# node-v2.net
KiCad netlist of a schematic drawn in EAGLE
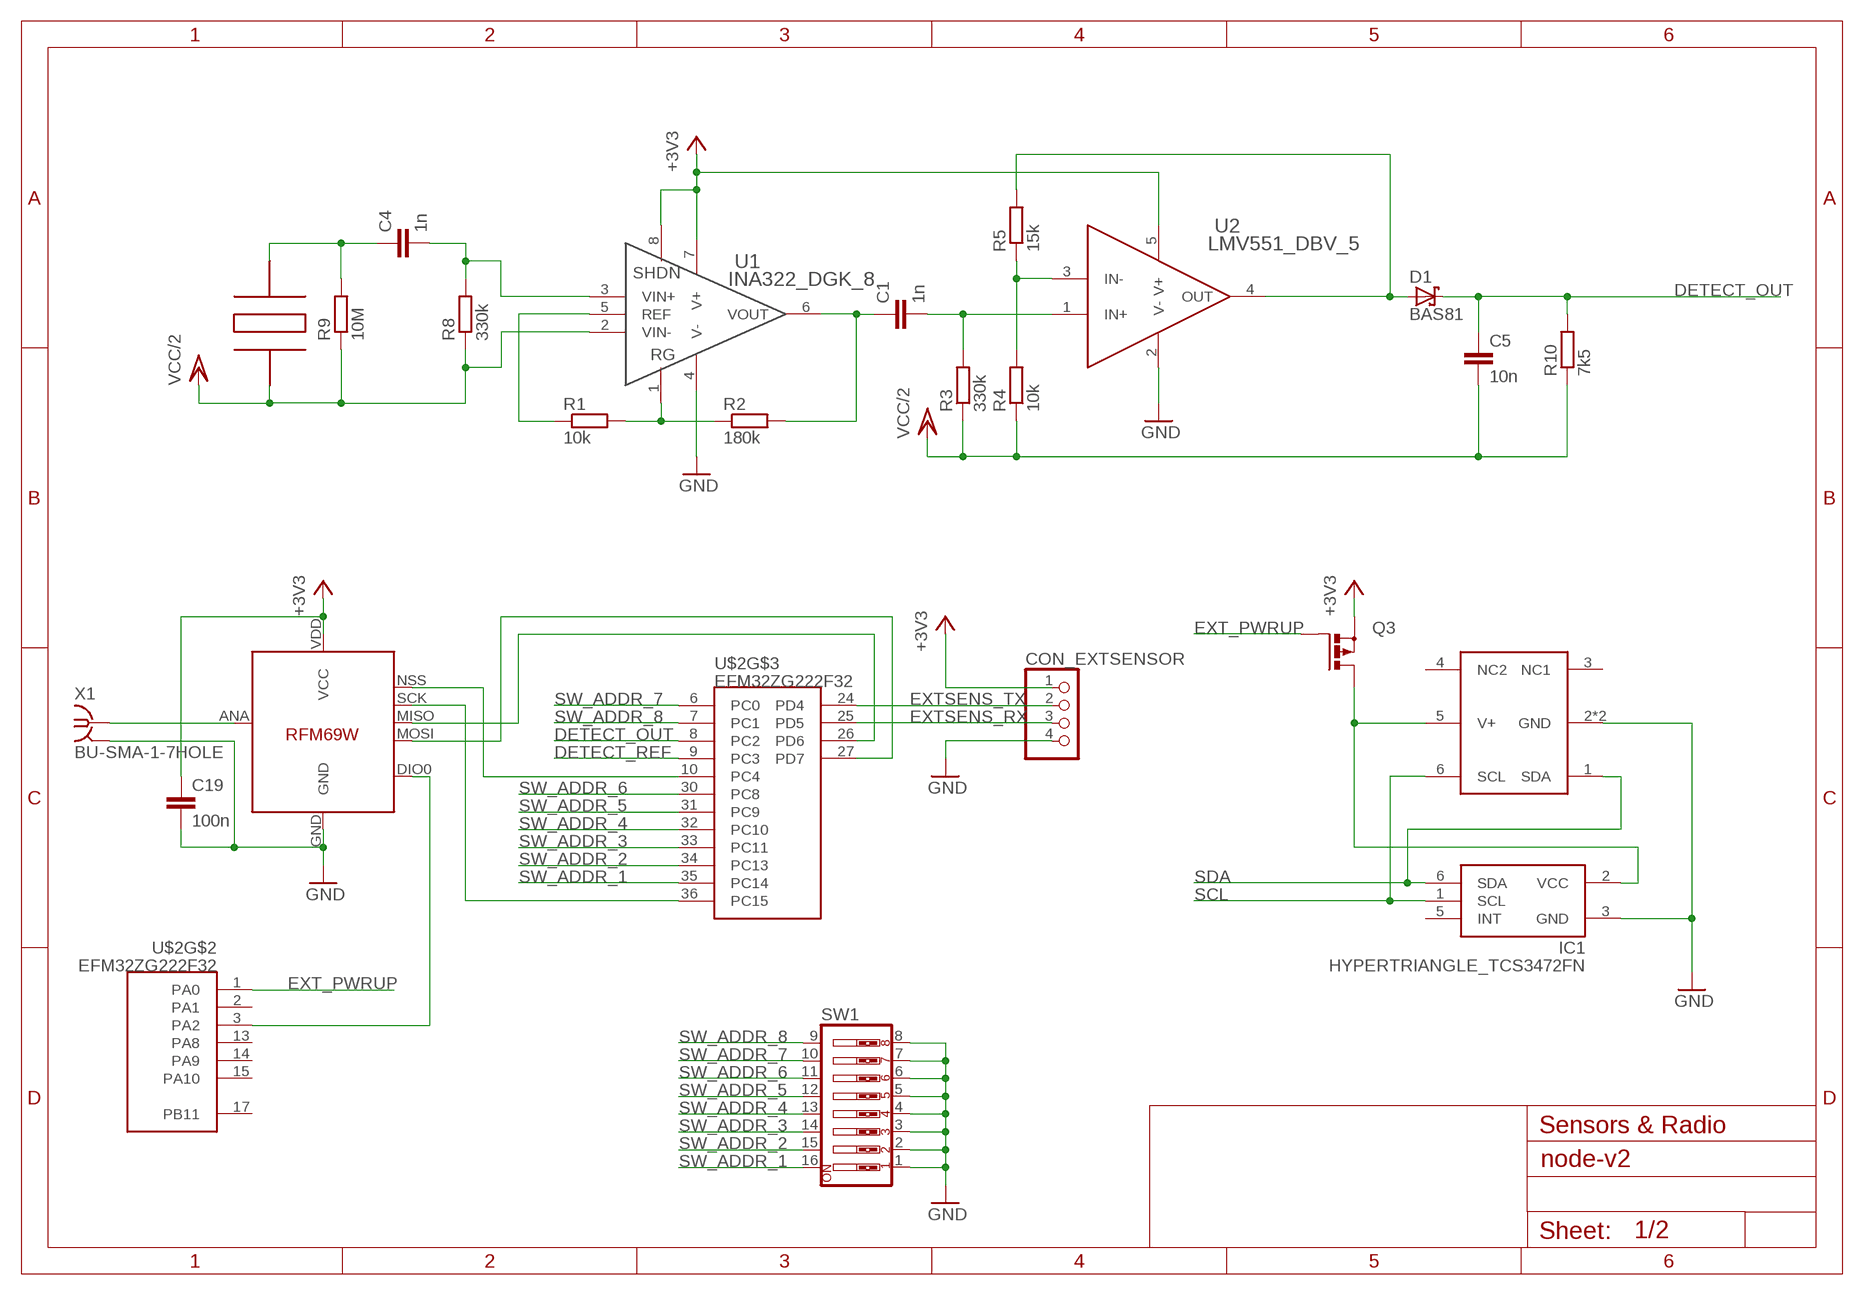
[diagram p0: schematic, sheet 1]
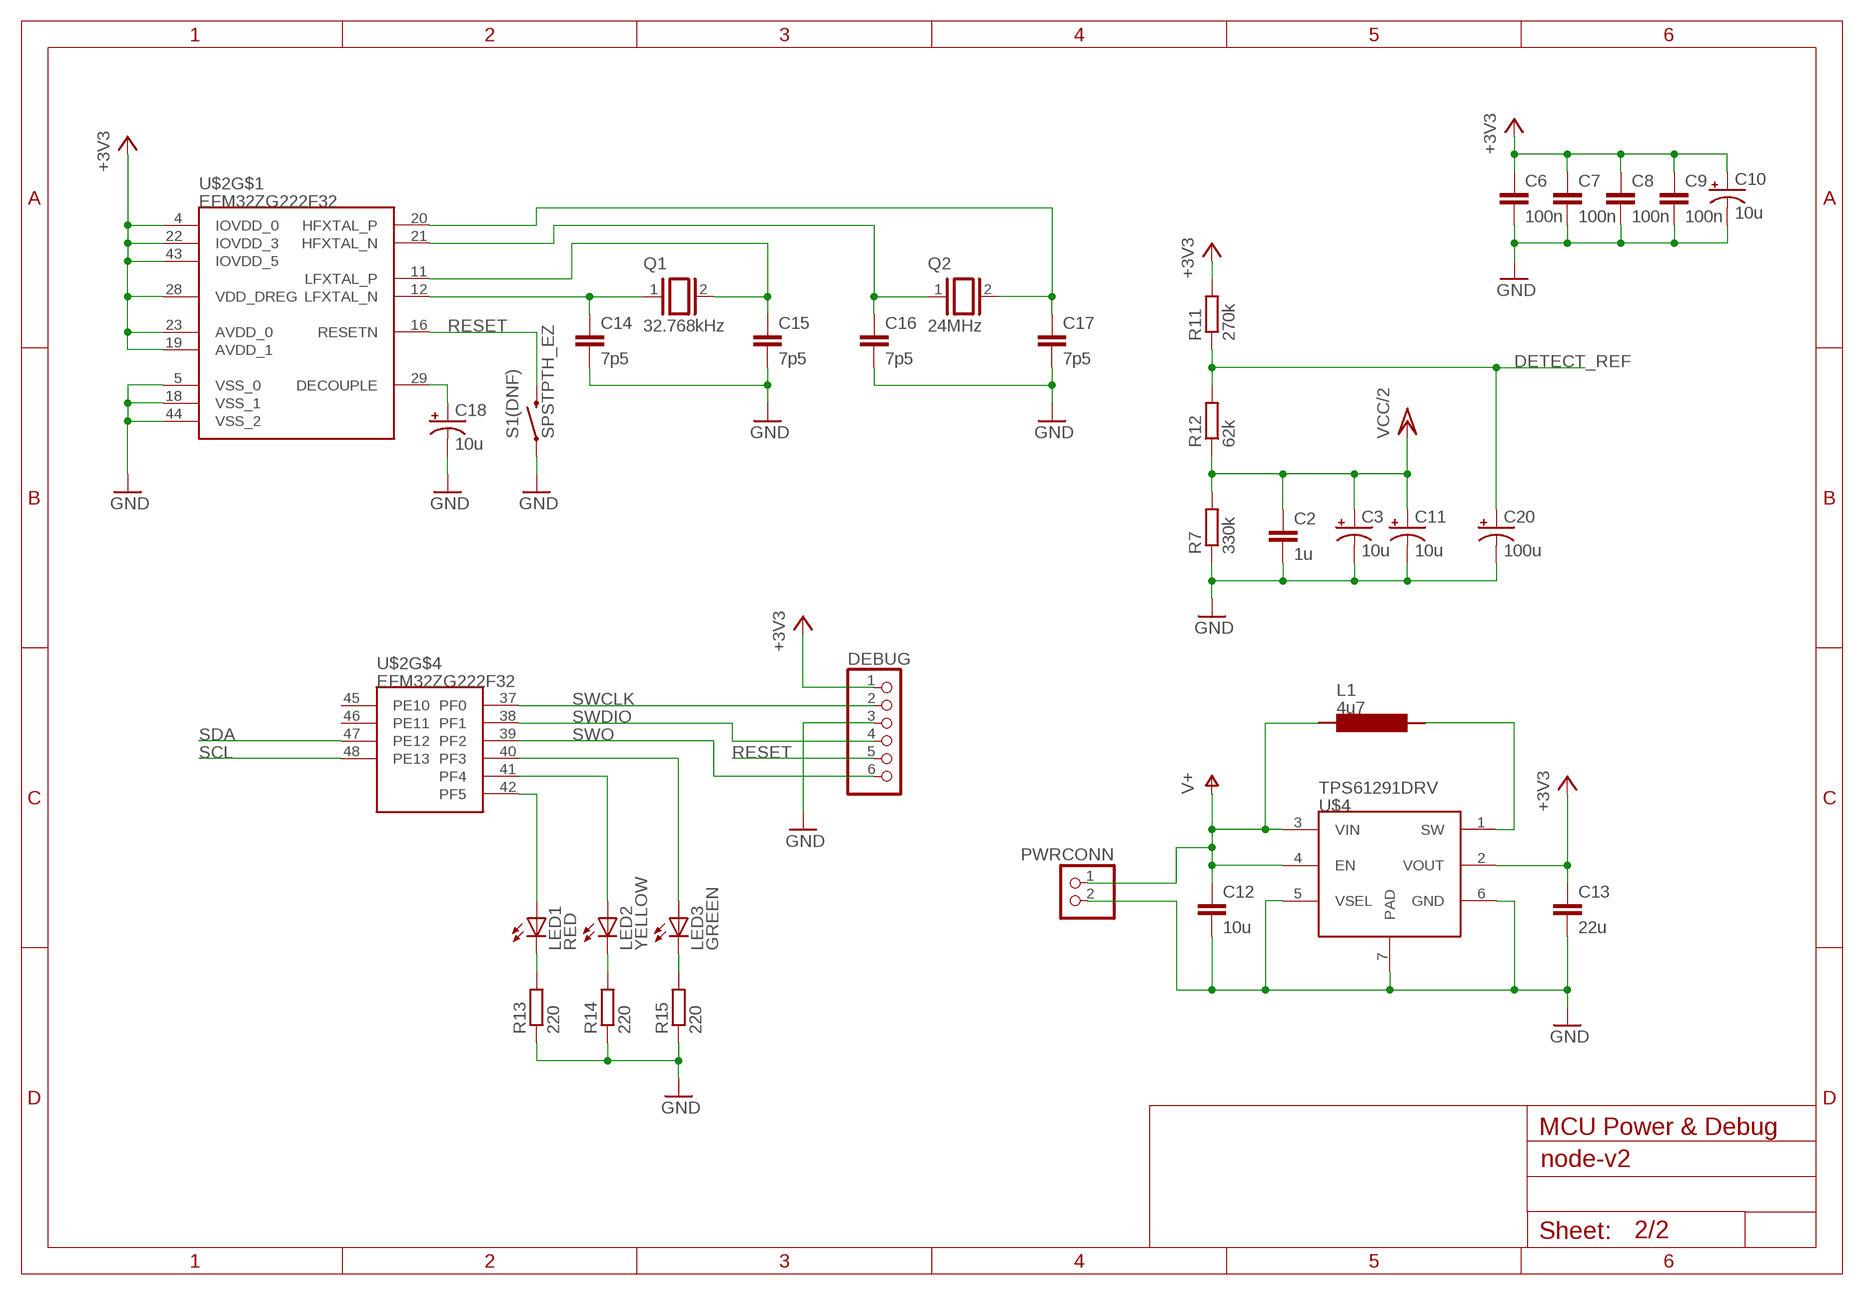
[diagram p1: schematic, sheet 2]

(export (version "E")
  (design (tool "Eeschema 10.0.6"))
  (components
    (comp (ref "C2")
      (value "1u")
      (footprint "eagle-import:CAP-PTH-SMALL")
      (libsource (lib "eagle-import") (part "CAPPTH"))
    )
    (comp (ref "C3")
      (value "10u")
      (footprint "eagle-import:CPOL-RADIAL-10UF-25V")
      (libsource (lib "eagle-import") (part "CAP_POLPTH2"))
    )
    (comp (ref "C6")
      (value "100n")
      (footprint "eagle-import:CAP-PTH-SMALL")
      (libsource (lib "eagle-import") (part "CAPPTH"))
    )
    (comp (ref "C7")
      (value "100n")
      (footprint "eagle-import:CAP-PTH-5MM")
      (libsource (lib "eagle-import") (part "CAPPTH1"))
    )
    (comp (ref "C8")
      (value "100n")
      (footprint "eagle-import:CAP-PTH-SMALL")
      (libsource (lib "eagle-import") (part "CAPPTH"))
    )
    (comp (ref "C9")
      (value "100n")
      (footprint "eagle-import:CAP-PTH-SMALL")
      (libsource (lib "eagle-import") (part "CAPPTH"))
    )
    (comp (ref "C10")
      (value "10u")
      (footprint "eagle-import:CPOL-RADIAL-10UF-25V")
      (libsource (lib "eagle-import") (part "CAP_POLPTH2"))
    )
    (comp (ref "C11")
      (value "10u")
      (footprint "eagle-import:CPOL-RADIAL-10UF-25V")
      (libsource (lib "eagle-import") (part "CAP_POLPTH2"))
    )
    (comp (ref "C12")
      (value "10u")
      (footprint "eagle-import:1206")
      (libsource (lib "eagle-import") (part "CAP1206"))
    )
    (comp (ref "C13")
      (value "22u")
      (footprint "eagle-import:1206")
      (libsource (lib "eagle-import") (part "CAP1206"))
    )
    (comp (ref "C14")
      (value "7p5")
      (footprint "eagle-import:CAP-PTH-SMALL")
      (libsource (lib "eagle-import") (part "CAPPTH"))
    )
    (comp (ref "C15")
      (value "7p5")
      (footprint "eagle-import:CAP-PTH-SMALL")
      (libsource (lib "eagle-import") (part "CAPPTH"))
    )
    (comp (ref "C16")
      (value "7p5")
      (footprint "eagle-import:CAP-PTH-SMALL")
      (libsource (lib "eagle-import") (part "CAPPTH"))
    )
    (comp (ref "C17")
      (value "7p5")
      (footprint "eagle-import:CAP-PTH-SMALL")
      (libsource (lib "eagle-import") (part "CAPPTH"))
    )
    (comp (ref "C18")
      (value "10u")
      (footprint "eagle-import:CPOL-RADIAL-10UF-25V")
      (libsource (lib "eagle-import") (part "CAP_POLPTH2"))
    )
    (comp (ref "C20")
      (value "100u")
      (footprint "eagle-import:CPOL-RADIAL-10UF-25V")
      (libsource (lib "eagle-import") (part "CAP_POLPTH2"))
    )
    (comp (ref "DEBUG")
      (value "PINHD-1X6")
      (footprint "eagle-import:1X06")
      (libsource (lib "eagle-import") (part "PINHD-1X6"))
    )
    (comp (ref "L1")
      (value "4u7")
      (footprint "eagle-import:LTF5022")
      (libsource (lib "eagle-import") (part "LTF5022"))
    )
    (comp (ref "LED1")
      (value "RED")
      (footprint "eagle-import:LED3MM")
      (libsource (lib "eagle-import") (part "LED3MM"))
    )
    (comp (ref "LED2")
      (value "YELLOW")
      (footprint "eagle-import:LED3MM")
      (libsource (lib "eagle-import") (part "LED3MM"))
    )
    (comp (ref "LED3")
      (value "GREEN")
      (footprint "eagle-import:LED3MM")
      (libsource (lib "eagle-import") (part "LED3MM"))
    )
    (comp (ref "PWRCONN")
      (value "PINHD-1X2")
      (footprint "eagle-import:1X02")
      (libsource (lib "eagle-import") (part "PINHD-1X2"))
    )
    (comp (ref "Q1")
      (value "32.768kHz")
      (footprint "eagle-import:QS")
      (libsource (lib "eagle-import") (part "XTAL/S"))
    )
    (comp (ref "Q2")
      (value "24MHz")
      (footprint "eagle-import:QS")
      (libsource (lib "eagle-import") (part "XTAL/S"))
    )
    (comp (ref "R7")
      (value "330k")
      (footprint "eagle-import:0204_7")
      (libsource (lib "eagle-import") (part "R-EU_0204/7"))
    )
    (comp (ref "R11")
      (value "270k")
      (footprint "eagle-import:0204_7")
      (libsource (lib "eagle-import") (part "R-EU_0204/7"))
    )
    (comp (ref "R12")
      (value "62k")
      (footprint "eagle-import:0204_7")
      (libsource (lib "eagle-import") (part "R-EU_0204/7"))
    )
    (comp (ref "R13")
      (value "220")
      (footprint "eagle-import:0204_7")
      (libsource (lib "eagle-import") (part "R-EU_0204/7"))
    )
    (comp (ref "R14")
      (value "220")
      (footprint "eagle-import:0204_7")
      (libsource (lib "eagle-import") (part "R-EU_0204/7"))
    )
    (comp (ref "R15")
      (value "220")
      (footprint "eagle-import:0204_7")
      (libsource (lib "eagle-import") (part "R-EU_0204/7"))
    )
    (comp (ref "S1(DNF)")
      (value "SPSTPTH_EZ")
      (footprint "eagle-import:TACTILE-PTH-EZ")
      (libsource (lib "eagle-import") (part "SPSTPTH_EZ"))
    )
    (comp (ref "U$2")
      (value "EFM32ZG222F32")
      (footprint "eagle-import:QFP48")
      (libsource (lib "eagle-import") (part "EFM32ZG222F32"))
    )
    (comp (ref "U$4")
      (value "TPS61291DRV")
      (footprint "eagle-import:DRV0006A")
      (libsource (lib "eagle-import") (part "TPS61291DRV"))
    )
    (comp (ref "C1")
      (value "1n")
      (footprint "eagle-import:CAP-PTH-SMALL")
      (libsource (lib "eagle-import") (part "CAPPTH"))
    )
    (comp (ref "C4")
      (value "1n")
      (footprint "eagle-import:CAP-PTH-SMALL")
      (libsource (lib "eagle-import") (part "CAPPTH"))
    )
    (comp (ref "C5")
      (value "10n")
      (footprint "eagle-import:CAP-PTH-SMALL")
      (libsource (lib "eagle-import") (part "CAPPTH"))
    )
    (comp (ref "C19")
      (value "100n")
      (footprint "eagle-import:CAP-PTH-SMALL")
      (libsource (lib "eagle-import") (part "CAPPTH"))
    )
    (comp (ref "CON_EXTSENSOR")
      (value "PINHD-1X4")
      (footprint "eagle-import:1X04")
      (libsource (lib "eagle-import") (part "PINHD-1X4"))
    )
    (comp (ref "D1")
      (value "BAS81")
      (footprint "eagle-import:DO35-7")
      (libsource (lib "eagle-import") (part "SCHOTTKY-DIODEDO35-7"))
    )
    (comp (ref "IC1")
      (value "HYPERTRIANGLE_TCS3472FN")
      (footprint "eagle-import:HYPERTRIANGLE_DFN-6")
      (libsource (lib "eagle-import") (part "HYPERTRIANGLE_TCS3472FN"))
    )
    (comp (ref "Q3")
      (value "PMOSFET_PTO220BH")
      (footprint "eagle-import:TO220BH")
      (libsource (lib "eagle-import") (part "PMOSFET_PTO220BH"))
    )
    (comp (ref "R1")
      (value "10k")
      (footprint "eagle-import:0204_7")
      (libsource (lib "eagle-import") (part "R-EU_0204/7"))
    )
    (comp (ref "R2")
      (value "180k")
      (footprint "eagle-import:0204_7")
      (libsource (lib "eagle-import") (part "R-EU_0204/7"))
    )
    (comp (ref "R3")
      (value "330k")
      (footprint "eagle-import:0204_7")
      (libsource (lib "eagle-import") (part "R-EU_0204/7"))
    )
    (comp (ref "R4")
      (value "10k")
      (footprint "eagle-import:0204_7")
      (libsource (lib "eagle-import") (part "R-EU_0204/7"))
    )
    (comp (ref "R5")
      (value "15k")
      (footprint "eagle-import:0204_7")
      (libsource (lib "eagle-import") (part "R-EU_0204/7"))
    )
    (comp (ref "R8")
      (value "330k")
      (footprint "eagle-import:0204_7")
      (libsource (lib "eagle-import") (part "R-EU_0204/7"))
    )
    (comp (ref "R9")
      (value "10M")
      (footprint "eagle-import:0204_7")
      (libsource (lib "eagle-import") (part "R-EU_0204/7"))
    )
    (comp (ref "R10")
      (value "7k5")
      (footprint "eagle-import:0204_7")
      (libsource (lib "eagle-import") (part "R-EU_0204/7"))
    )
    (comp (ref "RADIO")
      (value "RFM69")
      (footprint "eagle-import:RFM69W-MINPADS")
      (libsource (lib "eagle-import") (part "RFM69"))
    )
    (comp (ref "SW1")
      (value "SW_DIP-8")
      (footprint "eagle-import:DIPSWITCH-08")
      (libsource (lib "eagle-import") (part "SW_DIP-8"))
    )
    (comp (ref "U$1")
      (value "PIEZOWIREHEADER")
      (footprint "eagle-import:1X02")
      (libsource (lib "eagle-import") (part "PIEZOWIREHEADER"))
    )
    (comp (ref "U$3")
      (value "SHT21")
      (footprint "eagle-import:SHT21")
      (libsource (lib "eagle-import") (part "SHT21"))
    )
    (comp (ref "U1")
      (value "INA322_DGK_8")
      (footprint "eagle-import:DGK8")
      (fields
        (field (name "GENERIC_PART_NUMBER") "INA322")
        (field (name "MANUFACTURER") "Texas Instruments")
        (field (name "MANUFACTURER_PART_NUMBER") "ina322_dgk_8")
      )
      (libsource (lib "eagle-import") (part "INA322_DGK_8"))
    )
    (comp (ref "U2")
      (value "LMV551_DBV_5")
      (footprint "eagle-import:MF05A")
      (libsource (lib "eagle-import") (part "LMV551_DBV_5"))
    )
    (comp (ref "X1")
      (value "BU-SMA-1-7HOLE")
      (footprint "eagle-import:SMA_1-7HOLES")
      (libsource (lib "eagle-import") (part "BU-SMA-1-7HOLE"))
    )
  )
  (nets
    (net (code "1") (name "+3V3") (class "Default")
      (node (ref "C10") (pin "1") (pinfunction "+_1") (pintype "passive"))
      (node (ref "C13") (pin "1") (pinfunction "1_1") (pintype "passive"))
      (node (ref "C19") (pin "1") (pinfunction "1_1") (pintype "passive"))
      (node (ref "C6") (pin "1") (pinfunction "1_1") (pintype "passive"))
      (node (ref "C7") (pin "1") (pinfunction "1_1") (pintype "passive"))
      (node (ref "C8") (pin "1") (pinfunction "1_1") (pintype "passive"))
      (node (ref "C9") (pin "1") (pinfunction "1_1") (pintype "passive"))
      (node (ref "CON_EXTSENSOR") (pin "1") (pinfunction "1_1") (pintype "passive"))
      (node (ref "DEBUG") (pin "1") (pinfunction "1_1") (pintype "passive"))
      (node (ref "Q3") (pin "S") (pinfunction "S_S") (pintype "passive"))
      (node (ref "R11") (pin "2") (pinfunction "2_2") (pintype "passive"))
      (node (ref "RADIO") (pin "VDD") (pinfunction "VCC_VDD") (pintype "power_in"))
      (node (ref "U$2") (pin "19") (pinfunction "AVDD_1_19") (pintype "power_in"))
      (node (ref "U$2") (pin "22") (pinfunction "IOVDD_3_22") (pintype "power_in"))
      (node (ref "U$2") (pin "23") (pinfunction "AVDD_0_23") (pintype "power_in"))
      (node (ref "U$2") (pin "28") (pinfunction "VDD_DREG_28") (pintype "power_in"))
      (node (ref "U$2") (pin "4") (pinfunction "IOVDD_0_4") (pintype "power_in"))
      (node (ref "U$2") (pin "43") (pinfunction "IOVDD_5_43") (pintype "power_in"))
      (node (ref "U$4") (pin "2") (pinfunction "VOUT_2") (pintype "bidirectional"))
      (node (ref "U1") (pin "7") (pinfunction "V+_7") (pintype "power_in"))
      (node (ref "U1") (pin "8") (pinfunction "SHDN_8") (pintype "passive"))
      (node (ref "U2") (pin "5") (pinfunction "V+_5") (pintype "power_in"))
    )
    (net (code "2") (name "DETECT_OUT") (class "Default")
      (node (ref "C5") (pin "1") (pinfunction "1_1") (pintype "passive"))
      (node (ref "D1") (pin "C") (pinfunction "C_C") (pintype "passive"))
      (node (ref "R10") (pin "2") (pinfunction "2_2") (pintype "passive"))
      (node (ref "U$2") (pin "8") (pinfunction "PC2_8") (pintype "bidirectional"))
    )
    (net (code "3") (name "DETECT_REF") (class "Default")
      (node (ref "C20") (pin "1") (pinfunction "+_1") (pintype "passive"))
      (node (ref "R11") (pin "1") (pinfunction "1_1") (pintype "passive"))
      (node (ref "R12") (pin "2") (pinfunction "2_2") (pintype "passive"))
      (node (ref "U$2") (pin "9") (pinfunction "PC3_9") (pintype "bidirectional"))
    )
    (net (code "4") (name "EXTSENS_RX") (class "Default")
      (node (ref "CON_EXTSENSOR") (pin "3") (pinfunction "3_3") (pintype "passive"))
      (node (ref "U$2") (pin "25") (pinfunction "PD5_25") (pintype "bidirectional"))
    )
    (net (code "5") (name "EXTSENS_TX") (class "Default")
      (node (ref "CON_EXTSENSOR") (pin "2") (pinfunction "2_2") (pintype "passive"))
      (node (ref "U$2") (pin "24") (pinfunction "PD4_24") (pintype "bidirectional"))
    )
    (net (code "6") (name "EXT_PWRUP") (class "Default")
      (node (ref "Q3") (pin "G") (pinfunction "G_G") (pintype "passive"))
      (node (ref "U$2") (pin "1") (pinfunction "PA0_1") (pintype "bidirectional"))
    )
    (net (code "7") (name "GND") (class "Default")
      (node (ref "C10") (pin "2") (pinfunction "-_2") (pintype "passive"))
      (node (ref "C11") (pin "2") (pinfunction "-_2") (pintype "passive"))
      (node (ref "C12") (pin "2") (pinfunction "2_2") (pintype "passive"))
      (node (ref "C13") (pin "2") (pinfunction "2_2") (pintype "passive"))
      (node (ref "C14") (pin "2") (pinfunction "2_2") (pintype "passive"))
      (node (ref "C15") (pin "2") (pinfunction "2_2") (pintype "passive"))
      (node (ref "C16") (pin "2") (pinfunction "2_2") (pintype "passive"))
      (node (ref "C17") (pin "2") (pinfunction "2_2") (pintype "passive"))
      (node (ref "C18") (pin "2") (pinfunction "-_2") (pintype "passive"))
      (node (ref "C19") (pin "2") (pinfunction "2_2") (pintype "passive"))
      (node (ref "C2") (pin "2") (pinfunction "2_2") (pintype "passive"))
      (node (ref "C20") (pin "2") (pinfunction "-_2") (pintype "passive"))
      (node (ref "C3") (pin "2") (pinfunction "-_2") (pintype "passive"))
      (node (ref "C6") (pin "2") (pinfunction "2_2") (pintype "passive"))
      (node (ref "C7") (pin "2") (pinfunction "2_2") (pintype "passive"))
      (node (ref "C8") (pin "2") (pinfunction "2_2") (pintype "passive"))
      (node (ref "C9") (pin "2") (pinfunction "2_2") (pintype "passive"))
      (node (ref "CON_EXTSENSOR") (pin "4") (pinfunction "4_4") (pintype "passive"))
      (node (ref "DEBUG") (pin "3") (pinfunction "3_3") (pintype "passive"))
      (node (ref "IC1") (pin "3") (pinfunction "GND_3") (pintype "power_in"))
      (node (ref "PWRCONN") (pin "2") (pinfunction "2_2") (pintype "passive"))
      (node (ref "R13") (pin "1") (pinfunction "1_1") (pintype "passive"))
      (node (ref "R14") (pin "1") (pinfunction "1_1") (pintype "passive"))
      (node (ref "R15") (pin "1") (pinfunction "1_1") (pintype "passive"))
      (node (ref "R7") (pin "1") (pinfunction "1_1") (pintype "passive"))
      (node (ref "RADIO") (pin "GND") (pinfunction "GND_GND") (pintype "power_in"))
      (node (ref "S1(DNF)") (pin "1") (pinfunction "1_1") (pintype "passive"))
      (node (ref "SW1") (pin "1") (pinfunction "1_1") (pintype "passive"))
      (node (ref "SW1") (pin "2") (pinfunction "2_2") (pintype "passive"))
      (node (ref "SW1") (pin "3") (pinfunction "3_3") (pintype "passive"))
      (node (ref "SW1") (pin "4") (pinfunction "4_4") (pintype "passive"))
      (node (ref "SW1") (pin "5") (pinfunction "5_5") (pintype "passive"))
      (node (ref "SW1") (pin "6") (pinfunction "6_6") (pintype "passive"))
      (node (ref "SW1") (pin "7") (pinfunction "7_7") (pintype "passive"))
      (node (ref "SW1") (pin "8") (pinfunction "8_8") (pintype "passive"))
      (node (ref "U$2") (pin "18") (pinfunction "VSS_1_18") (pintype "bidirectional"))
      (node (ref "U$2") (pin "44") (pinfunction "VSS_2_44") (pintype "bidirectional"))
      (node (ref "U$2") (pin "5") (pinfunction "VSS_0_5") (pintype "bidirectional"))
      (node (ref "U$3") (pin "2") (pinfunction "GND_2") (pintype "bidirectional"))
      (node (ref "U$3") (pin "P$1") (pinfunction "GND_P$1") (pintype "bidirectional"))
      (node (ref "U$4") (pin "5") (pinfunction "VSEL_5") (pintype "bidirectional"))
      (node (ref "U$4") (pin "6") (pinfunction "GND_6") (pintype "bidirectional"))
      (node (ref "U$4") (pin "7") (pinfunction "PAD_7") (pintype "bidirectional"))
      (node (ref "U1") (pin "4") (pinfunction "V-_4") (pintype "power_in"))
      (node (ref "U2") (pin "2") (pinfunction "V-_2") (pintype "power_in"))
      (node (ref "X1") (pin "2") (pinfunction "2_2") (pintype "passive"))
      (node (ref "X1") (pin "3") (pinfunction "2_3") (pintype "passive"))
      (node (ref "X1") (pin "4") (pinfunction "2_4") (pintype "passive"))
      (node (ref "X1") (pin "5") (pinfunction "2_5") (pintype "passive"))
    )
    (net (code "8") (name "Net-(C18-+)") (class "Default")
      (node (ref "C18") (pin "1") (pinfunction "+_1") (pintype "passive"))
      (node (ref "U$2") (pin "29") (pinfunction "DECOUPLE_29") (pintype "power_in"))
    )
    (net (code "9") (name "Net-(IC1-VCC)") (class "Default")
      (node (ref "IC1") (pin "2") (pinfunction "VCC_2") (pintype "power_in"))
      (node (ref "Q3") (pin "D") (pinfunction "D_D") (pintype "passive"))
      (node (ref "U$3") (pin "5") (pinfunction "V+_5") (pintype "bidirectional"))
    )
    (net (code "10") (name "Net-(LED1-C)") (class "Default")
      (node (ref "LED1") (pin "K") (pinfunction "C_K") (pintype "passive"))
      (node (ref "R13") (pin "2") (pinfunction "2_2") (pintype "passive"))
    )
    (net (code "11") (name "Net-(LED2-C)") (class "Default")
      (node (ref "LED2") (pin "K") (pinfunction "C_K") (pintype "passive"))
      (node (ref "R14") (pin "2") (pinfunction "2_2") (pintype "passive"))
    )
    (net (code "12") (name "Net-(LED3-C)") (class "Default")
      (node (ref "LED3") (pin "K") (pinfunction "C_K") (pintype "passive"))
      (node (ref "R15") (pin "2") (pinfunction "2_2") (pintype "passive"))
    )
    (net (code "13") (name "Net-(RADIO-ANT)") (class "Default")
      (node (ref "RADIO") (pin "ANA") (pinfunction "ANT_ANA") (pintype "passive"))
      (node (ref "X1") (pin "1") (pinfunction "1_1") (pintype "passive"))
    )
    (net (code "14") (name "Net-(RADIO-SEL)") (class "Default")
      (node (ref "RADIO") (pin "NSS") (pinfunction "SEL_NSS") (pintype "input"))
      (node (ref "U$2") (pin "10") (pinfunction "PC4_10") (pintype "bidirectional"))
    )
    (net (code "15") (name "Net-(U$1-S+)") (class "Default")
      (node (ref "C4") (pin "1") (pinfunction "1_1") (pintype "passive"))
      (node (ref "R9") (pin "2") (pinfunction "2_2") (pintype "passive"))
      (node (ref "U$1") (pin "1") (pinfunction "S+_1") (pintype "passive"))
    )
    (net (code "16") (name "Net-(U$2A-HFXTAL_N)") (class "Default")
      (node (ref "C16") (pin "1") (pinfunction "1_1") (pintype "passive"))
      (node (ref "Q2") (pin "1") (pinfunction "1_1") (pintype "passive"))
      (node (ref "U$2") (pin "21") (pinfunction "HFXTAL_N_21") (pintype "bidirectional"))
    )
    (net (code "17") (name "Net-(U$2A-HFXTAL_P)") (class "Default")
      (node (ref "C17") (pin "1") (pinfunction "1_1") (pintype "passive"))
      (node (ref "Q2") (pin "2") (pinfunction "2_2") (pintype "passive"))
      (node (ref "U$2") (pin "20") (pinfunction "HFXTAL_P_20") (pintype "bidirectional"))
    )
    (net (code "18") (name "Net-(U$2A-LFXTAL_N)") (class "Default")
      (node (ref "C14") (pin "1") (pinfunction "1_1") (pintype "passive"))
      (node (ref "Q1") (pin "1") (pinfunction "1_1") (pintype "passive"))
      (node (ref "U$2") (pin "12") (pinfunction "LFXTAL_N_12") (pintype "bidirectional"))
    )
    (net (code "19") (name "Net-(U$2A-LFXTAL_P)") (class "Default")
      (node (ref "C15") (pin "1") (pinfunction "1_1") (pintype "passive"))
      (node (ref "Q1") (pin "2") (pinfunction "2_2") (pintype "passive"))
      (node (ref "U$2") (pin "11") (pinfunction "LFXTAL_P_11") (pintype "bidirectional"))
    )
    (net (code "20") (name "Net-(U$2B-PA2)") (class "Default")
      (node (ref "RADIO") (pin "DIO0") (pinfunction "DIO0_DIO0") (pintype "open_collector"))
      (node (ref "U$2") (pin "3") (pinfunction "PA2_3") (pintype "bidirectional"))
    )
    (net (code "21") (name "Net-(U$2C-PC15)") (class "Default")
      (node (ref "RADIO") (pin "SCK") (pinfunction "SCK_SCK") (pintype "input"))
      (node (ref "U$2") (pin "36") (pinfunction "PC15_36") (pintype "bidirectional"))
    )
    (net (code "22") (name "Net-(U$2C-PD6)") (class "Default")
      (node (ref "RADIO") (pin "MISO") (pinfunction "MISO_MISO") (pintype "input"))
      (node (ref "U$2") (pin "26") (pinfunction "PD6_26") (pintype "bidirectional"))
    )
    (net (code "23") (name "Net-(U$2C-PD7)") (class "Default")
      (node (ref "RADIO") (pin "MOSI") (pinfunction "MOSI_MOSI") (pintype "output"))
      (node (ref "U$2") (pin "27") (pinfunction "PD7_27") (pintype "bidirectional"))
    )
    (net (code "24") (name "Net-(U$2D-PF3)") (class "Default")
      (node (ref "LED3") (pin "A") (pinfunction "A_A") (pintype "passive"))
      (node (ref "U$2") (pin "40") (pinfunction "PF3_40") (pintype "bidirectional"))
    )
    (net (code "25") (name "Net-(U$2D-PF4)") (class "Default")
      (node (ref "LED2") (pin "A") (pinfunction "A_A") (pintype "passive"))
      (node (ref "U$2") (pin "41") (pinfunction "PF4_41") (pintype "bidirectional"))
    )
    (net (code "26") (name "Net-(U$2D-PF5)") (class "Default")
      (node (ref "LED1") (pin "A") (pinfunction "A_A") (pintype "passive"))
      (node (ref "U$2") (pin "42") (pinfunction "PF5_42") (pintype "bidirectional"))
    )
    (net (code "27") (name "Net-(U$4-SW)") (class "Default")
      (node (ref "L1") (pin "2") (pinfunction "2_2") (pintype "passive"))
      (node (ref "U$4") (pin "1") (pinfunction "SW_1") (pintype "bidirectional"))
    )
    (net (code "28") (name "Net-(U1-REF)") (class "Default")
      (node (ref "R1") (pin "1") (pinfunction "1_1") (pintype "passive"))
      (node (ref "U1") (pin "5") (pinfunction "REF_5") (pintype "passive"))
    )
    (net (code "29") (name "Net-(U1-RG)") (class "Default")
      (node (ref "R1") (pin "2") (pinfunction "2_2") (pintype "passive"))
      (node (ref "R2") (pin "1") (pinfunction "1_1") (pintype "passive"))
      (node (ref "U1") (pin "1") (pinfunction "RG_1") (pintype "passive"))
    )
    (net (code "30") (name "Net-(U1-VIN+)") (class "Default")
      (node (ref "C4") (pin "2") (pinfunction "2_2") (pintype "passive"))
      (node (ref "R8") (pin "2") (pinfunction "2_2") (pintype "passive"))
      (node (ref "U1") (pin "3") (pinfunction "VIN+_3") (pintype "input"))
    )
    (net (code "31") (name "Net-(U1-VOUT)") (class "Default")
      (node (ref "C1") (pin "1") (pinfunction "1_1") (pintype "passive"))
      (node (ref "R2") (pin "2") (pinfunction "2_2") (pintype "passive"))
      (node (ref "U1") (pin "6") (pinfunction "VOUT_6") (pintype "output"))
    )
    (net (code "32") (name "Net-(U2-IN+)") (class "Default")
      (node (ref "C1") (pin "2") (pinfunction "2_2") (pintype "passive"))
      (node (ref "R3") (pin "2") (pinfunction "2_2") (pintype "passive"))
      (node (ref "U2") (pin "1") (pinfunction "IN+_1") (pintype "input"))
    )
    (net (code "33") (name "Net-(U2-IN-)") (class "Default")
      (node (ref "R4") (pin "2") (pinfunction "2_2") (pintype "passive"))
      (node (ref "R5") (pin "1") (pinfunction "1_1") (pintype "passive"))
      (node (ref "U2") (pin "3") (pinfunction "IN-_3") (pintype "input"))
    )
    (net (code "34") (name "Net-(U2-OUT)") (class "Default")
      (node (ref "D1") (pin "A") (pinfunction "A_A") (pintype "passive"))
      (node (ref "R5") (pin "2") (pinfunction "2_2") (pintype "passive"))
      (node (ref "U2") (pin "4") (pinfunction "OUT_4") (pintype "output"))
    )
    (net (code "35") (name "RESET") (class "Default")
      (node (ref "DEBUG") (pin "5") (pinfunction "5_5") (pintype "passive"))
      (node (ref "S1(DNF)") (pin "3") (pinfunction "2_3") (pintype "passive"))
      (node (ref "U$2") (pin "16") (pinfunction "RESETN_16") (pintype "power_in"))
    )
    (net (code "36") (name "SCL") (class "Default")
      (node (ref "IC1") (pin "1") (pinfunction "SCL_1") (pintype "bidirectional"))
      (node (ref "U$2") (pin "48") (pinfunction "PE13_48") (pintype "bidirectional"))
      (node (ref "U$3") (pin "6") (pinfunction "SCL_6") (pintype "bidirectional"))
    )
    (net (code "37") (name "SDA") (class "Default")
      (node (ref "IC1") (pin "6") (pinfunction "SDA_6") (pintype "bidirectional"))
      (node (ref "U$2") (pin "47") (pinfunction "PE12_47") (pintype "bidirectional"))
      (node (ref "U$3") (pin "1") (pinfunction "SDA_1") (pintype "bidirectional"))
    )
    (net (code "38") (name "SWCLK") (class "Default")
      (node (ref "DEBUG") (pin "2") (pinfunction "2_2") (pintype "passive"))
      (node (ref "U$2") (pin "37") (pinfunction "PF0_37") (pintype "bidirectional"))
    )
    (net (code "39") (name "SWDIO") (class "Default")
      (node (ref "DEBUG") (pin "4") (pinfunction "4_4") (pintype "passive"))
      (node (ref "U$2") (pin "38") (pinfunction "PF1_38") (pintype "bidirectional"))
    )
    (net (code "40") (name "SWO") (class "Default")
      (node (ref "DEBUG") (pin "6") (pinfunction "6_6") (pintype "passive"))
      (node (ref "U$2") (pin "39") (pinfunction "PF2_39") (pintype "bidirectional"))
    )
    (net (code "41") (name "SW_ADDR_1") (class "Default")
      (node (ref "SW1") (pin "16") (pinfunction "16_16") (pintype "passive"))
      (node (ref "U$2") (pin "35") (pinfunction "PC14_35") (pintype "bidirectional"))
    )
    (net (code "42") (name "SW_ADDR_2") (class "Default")
      (node (ref "SW1") (pin "15") (pinfunction "15_15") (pintype "passive"))
      (node (ref "U$2") (pin "34") (pinfunction "PC13_34") (pintype "bidirectional"))
    )
    (net (code "43") (name "SW_ADDR_3") (class "Default")
      (node (ref "SW1") (pin "14") (pinfunction "14_14") (pintype "passive"))
      (node (ref "U$2") (pin "33") (pinfunction "PC11_33") (pintype "bidirectional"))
    )
    (net (code "44") (name "SW_ADDR_4") (class "Default")
      (node (ref "SW1") (pin "13") (pinfunction "13_13") (pintype "passive"))
      (node (ref "U$2") (pin "32") (pinfunction "PC10_32") (pintype "bidirectional"))
    )
    (net (code "45") (name "SW_ADDR_5") (class "Default")
      (node (ref "SW1") (pin "12") (pinfunction "12_12") (pintype "passive"))
      (node (ref "U$2") (pin "31") (pinfunction "PC9_31") (pintype "bidirectional"))
    )
    (net (code "46") (name "SW_ADDR_6") (class "Default")
      (node (ref "SW1") (pin "11") (pinfunction "11_11") (pintype "passive"))
      (node (ref "U$2") (pin "30") (pinfunction "PC8_30") (pintype "bidirectional"))
    )
    (net (code "47") (name "SW_ADDR_7") (class "Default")
      (node (ref "SW1") (pin "10") (pinfunction "10_10") (pintype "passive"))
      (node (ref "U$2") (pin "6") (pinfunction "PC0_6") (pintype "bidirectional"))
    )
    (net (code "48") (name "SW_ADDR_8") (class "Default")
      (node (ref "SW1") (pin "9") (pinfunction "9_9") (pintype "passive"))
      (node (ref "U$2") (pin "7") (pinfunction "PC1_7") (pintype "bidirectional"))
    )
    (net (code "49") (name "V+") (class "Default")
      (node (ref "C12") (pin "1") (pinfunction "1_1") (pintype "passive"))
      (node (ref "L1") (pin "1") (pinfunction "1_1") (pintype "passive"))
      (node (ref "PWRCONN") (pin "1") (pinfunction "1_1") (pintype "passive"))
      (node (ref "U$4") (pin "3") (pinfunction "VIN_3") (pintype "bidirectional"))
      (node (ref "U$4") (pin "4") (pinfunction "EN_4") (pintype "bidirectional"))
    )
    (net (code "50") (name "VCC{slash}2") (class "Default")
      (node (ref "C11") (pin "1") (pinfunction "+_1") (pintype "passive"))
      (node (ref "C2") (pin "1") (pinfunction "1_1") (pintype "passive"))
      (node (ref "C3") (pin "1") (pinfunction "+_1") (pintype "passive"))
      (node (ref "C5") (pin "2") (pinfunction "2_2") (pintype "passive"))
      (node (ref "R10") (pin "1") (pinfunction "1_1") (pintype "passive"))
      (node (ref "R12") (pin "1") (pinfunction "1_1") (pintype "passive"))
      (node (ref "R3") (pin "1") (pinfunction "1_1") (pintype "passive"))
      (node (ref "R4") (pin "1") (pinfunction "1_1") (pintype "passive"))
      (node (ref "R7") (pin "2") (pinfunction "2_2") (pintype "passive"))
      (node (ref "R8") (pin "1") (pinfunction "1_1") (pintype "passive"))
      (node (ref "R9") (pin "1") (pinfunction "1_1") (pintype "passive"))
      (node (ref "U$1") (pin "2") (pinfunction "S-_2") (pintype "passive"))
      (node (ref "U1") (pin "2") (pinfunction "VIN-_2") (pintype "input"))
    )
    (net (code "51") (name "unconnected-(IC1-INT-Pad5)") (class "Default")
      (node (ref "IC1") (pin "5") (pinfunction "INT_5") (pintype "output"))
    )
    (net (code "52") (name "unconnected-(U$2B-PA1-Pad2)") (class "Default")
      (node (ref "U$2") (pin "2") (pinfunction "PA1_2") (pintype "bidirectional"))
    )
    (net (code "53") (name "unconnected-(U$2B-PA8-Pad13)") (class "Default")
      (node (ref "U$2") (pin "13") (pinfunction "PA8_13") (pintype "bidirectional"))
    )
    (net (code "54") (name "unconnected-(U$2B-PA9-Pad14)") (class "Default")
      (node (ref "U$2") (pin "14") (pinfunction "PA9_14") (pintype "bidirectional"))
    )
    (net (code "55") (name "unconnected-(U$2B-PA10-Pad15)") (class "Default")
      (node (ref "U$2") (pin "15") (pinfunction "PA10_15") (pintype "bidirectional"))
    )
    (net (code "56") (name "unconnected-(U$2B-PB11-Pad17)") (class "Default")
      (node (ref "U$2") (pin "17") (pinfunction "PB11_17") (pintype "bidirectional"))
    )
    (net (code "57") (name "unconnected-(U$2D-PE10-Pad45)") (class "Default")
      (node (ref "U$2") (pin "45") (pinfunction "PE10_45") (pintype "bidirectional"))
    )
    (net (code "58") (name "unconnected-(U$2D-PE11-Pad46)") (class "Default")
      (node (ref "U$2") (pin "46") (pinfunction "PE11_46") (pintype "bidirectional"))
    )
    (net (code "59") (name "unconnected-(U$3-NC1-Pad3)") (class "Default")
      (node (ref "U$3") (pin "3") (pinfunction "NC1_3") (pintype "bidirectional"))
    )
    (net (code "60") (name "unconnected-(U$3-NC2-Pad4)") (class "Default")
      (node (ref "U$3") (pin "4") (pinfunction "NC2_4") (pintype "bidirectional"))
    )
  )
)
